# Power.net
KiCad netlist of a schematic drawn in Altium Designer
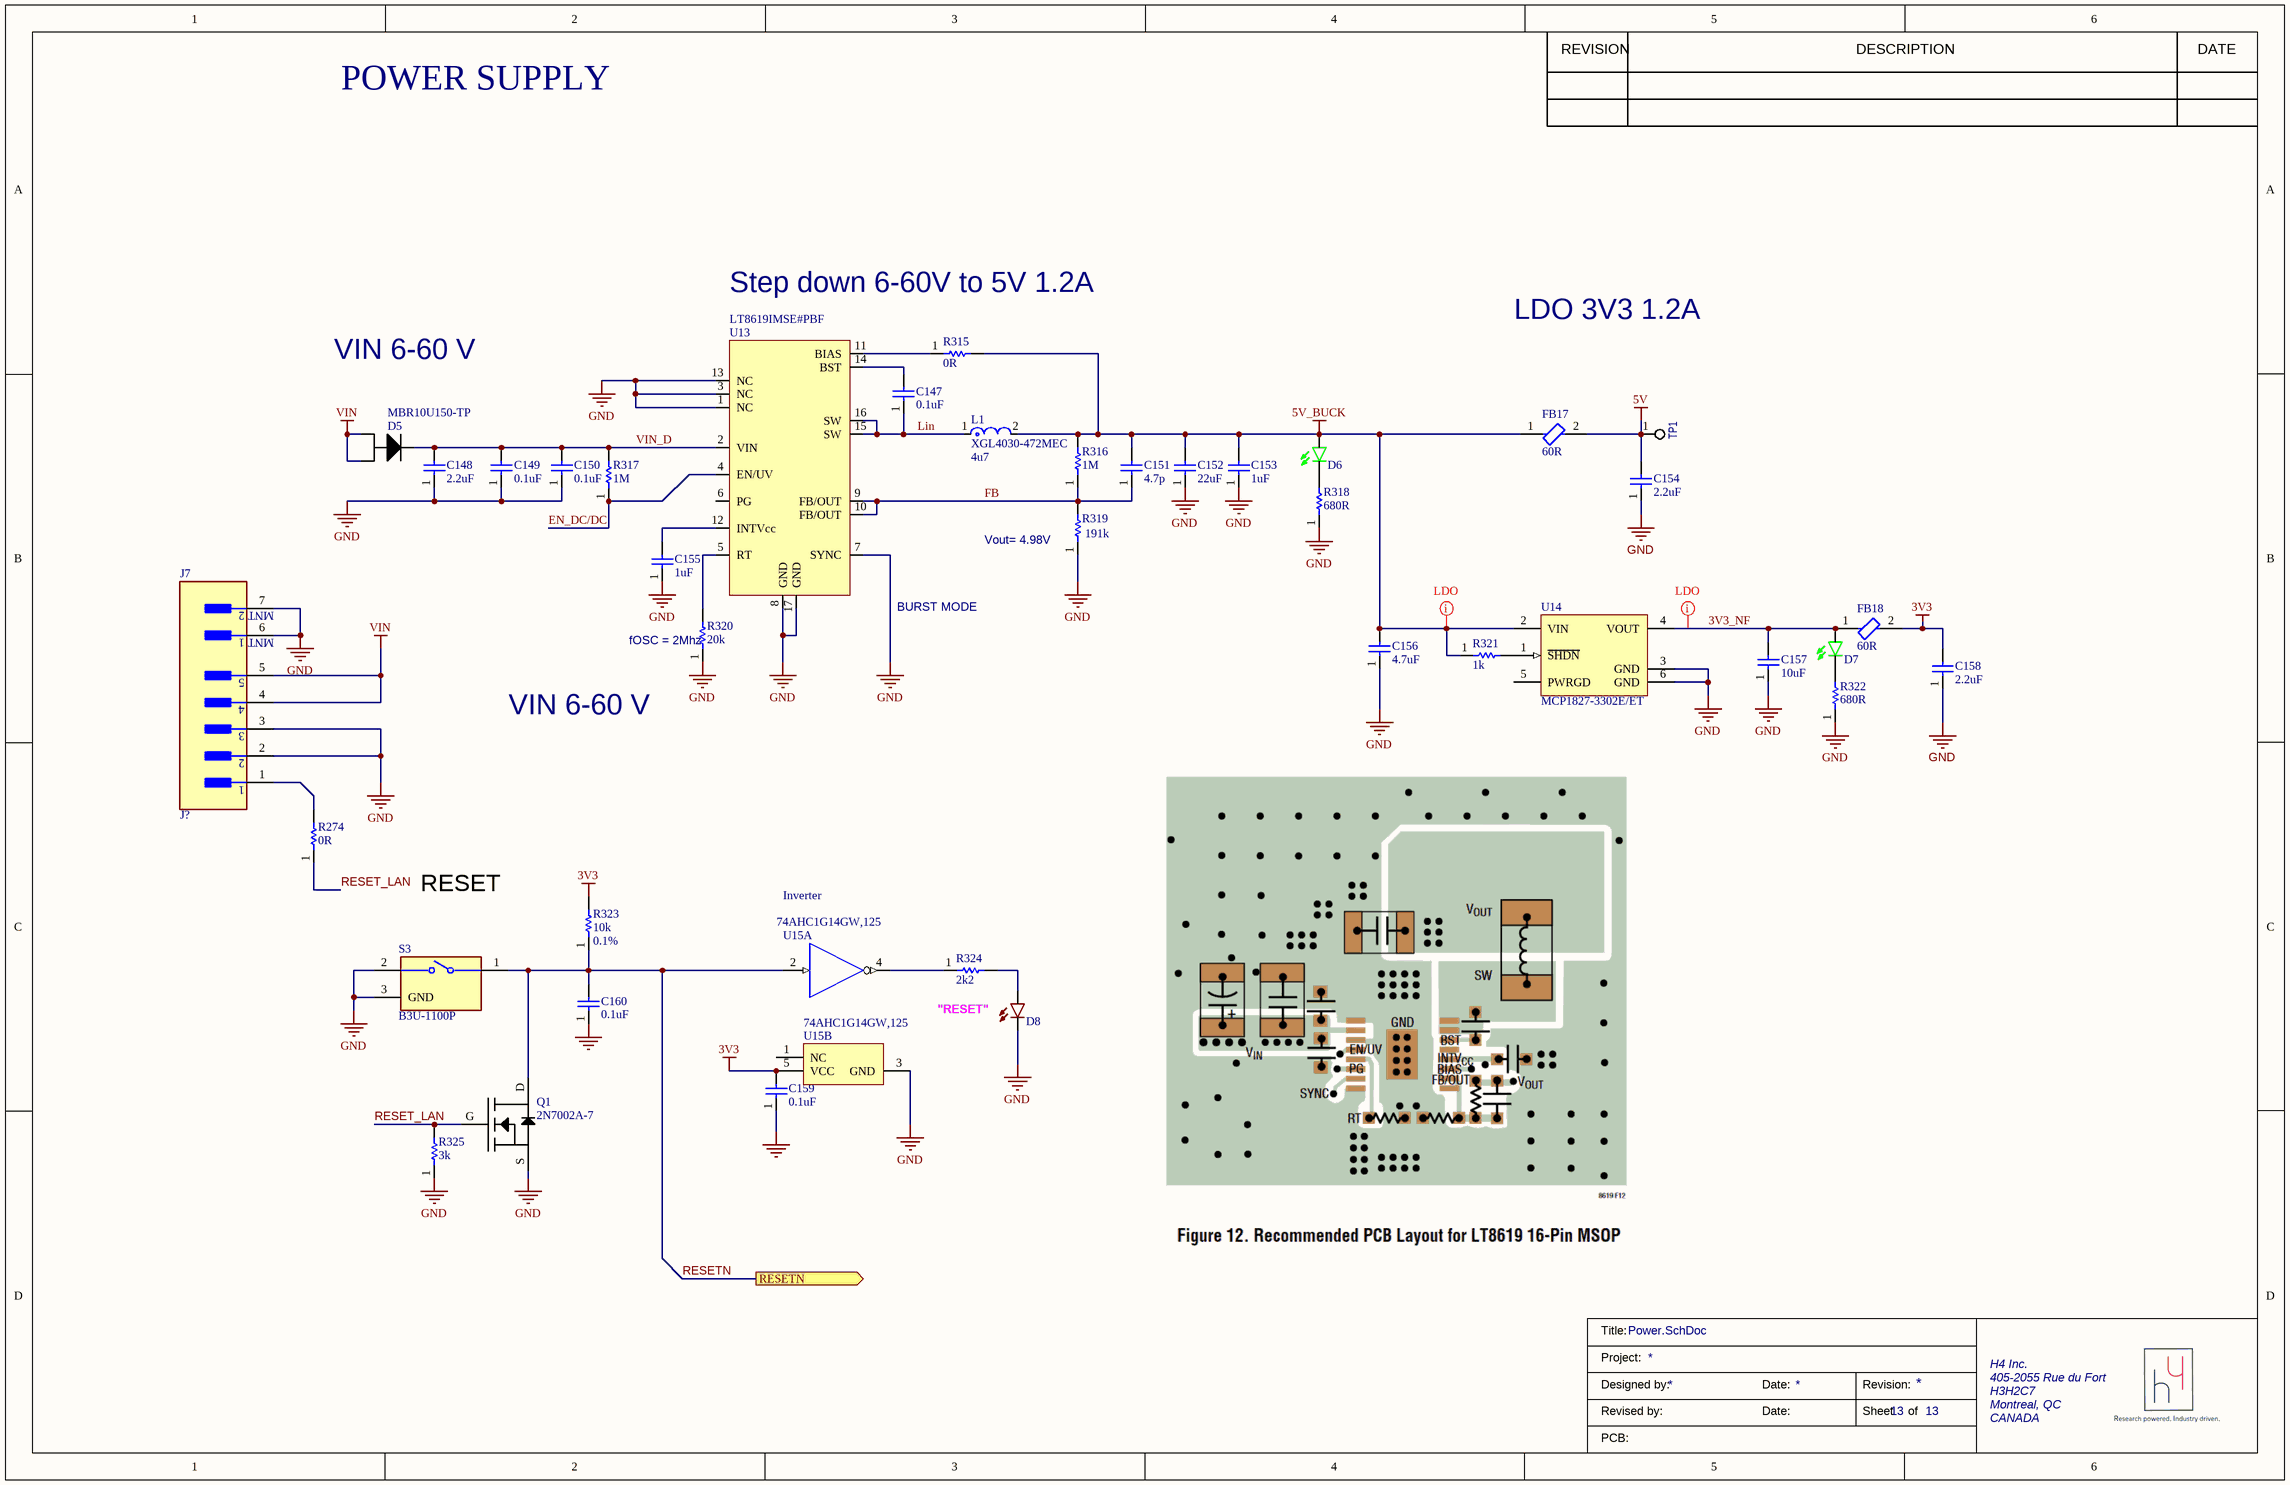
[diagram p0: Power.SchDoc]

(export (version "E")
  (design (tool "Eeschema 10.0.6"))
  (components
    (comp (ref "C147")
      (value "0.1uF")
      (footprint "CAPC1608X09N(0603)")
      (description "CAP CER 0.1UF 100V X7R 0603")
      (fields (field (name "MPN") "CL10B104KC8NNNC") (field (name "TOLERANCE") "10%"))
      (libsource (lib "IHMC_Altium_Lib") (part "0.1uF_100V_0603_CAP"))
    )
    (comp (ref "C148")
      (value "2.2uF")
      (footprint "CAPC3216X16N(1206)")
      (description "CAP CER 2.2UF 100V X7S 1206")
      (fields (field (name "MPN") "C3216X7S2A225K160AB") (field (name "TOLERANCE") "10%"))
      (libsource (lib "IHMC_Altium_Lib") (part "2.2uF_100V_1206_Cap"))
    )
    (comp (ref "C149")
      (value "0.1uF")
      (footprint "CAPC1608X09N(0603)")
      (description "CAP CER 0.1UF 100V X7R 0603")
      (fields (field (name "MPN") "CL10B104KC8NNNC") (field (name "TOLERANCE") "10%"))
      (libsource (lib "IHMC_Altium_Lib") (part "0.1uF_100V_0603_CAP"))
    )
    (comp (ref "C150")
      (value "0.1uF")
      (footprint "CAPC1608X09N(0603)")
      (description "CAP CER 0.1UF 100V X7R 0603")
      (fields (field (name "MPN") "CL10B104KC8NNNC") (field (name "TOLERANCE") "10%"))
      (libsource (lib "IHMC_Altium_Lib") (part "0.1uF_100V_0603_CAP"))
    )
    (comp (ref "C151")
      (value "4.7p")
      (footprint "0402_C")
      (fields
        (field (name "MANUFACTURER") "TDK")
        (field (name "MANUFACTURER PART NUMBER") "CGA2B2C0G1H4R7C050BA")
      )
      (libsource (lib "IHMC_Altium_Lib") (part "4p7_0402_50V_C0G_  CGA2B2C0G1H4R7C050BA"))
    )
    (comp (ref "C152")
      (value "22uF")
      (footprint "CAPC1608X09N(0603)")
      (description "CAP CER 22UF 10V X5R 0603")
      (fields (field (name "MPN") "C1608X5R1A226M080AC") (field (name "TOLERANCE") "20%"))
      (libsource (lib "IHMC_Altium_Lib") (part "22uF_10V_0603_CAP"))
    )
    (comp (ref "C153")
      (value "1uF")
      (footprint "CAPC1608X09N(0603)")
      (description "MLCC - SMD/SMT 25volts 1uF X5R 10%")
      (fields
        (field (name "MPN") "C0603C105K3PACTU")
        (field (name "VOLTAGE") "25VDC")
        (field (name "DRAWN BY") "TC")
      )
      (libsource (lib "IHMC_Altium_Lib") (part "1uF_25VDC_0603_Cap"))
    )
    (comp (ref "C154")
      (value "2.2uF")
      (footprint "CAPC1608X09N(0603)")
      (description "CAP CER 2.2UF 10V X5R 0603")
      (fields (field (name "MPN") "GRM188R61A225KE34D") (field (name "TOLERANCE") "10%"))
      (libsource (lib "IHMC_Altium_Lib") (part "2.2uF_10V_0603_CAP"))
    )
    (comp (ref "C155")
      (value "1uF")
      (footprint "CAPC1608X09N(0603)")
      (description "MLCC - SMD/SMT 25volts 1uF X5R 10%")
      (fields
        (field (name "MPN") "C0603C105K3PACTU")
        (field (name "VOLTAGE") "25VDC")
        (field (name "DRAWN BY") "TC")
      )
      (libsource (lib "IHMC_Altium_Lib") (part "1uF_25VDC_0603_Cap"))
    )
    (comp (ref "C156")
      (value "4.7uF")
      (footprint "CAPC1608X09N(0603)")
      (description "CAP CER 4.7UF 10V X5R 0603")
      (fields (field (name "MPN") "CL10A475KP8NNNC"))
      (libsource (lib "IHMC_Altium_Lib") (part "4.7uF_10V_0603_CAP"))
    )
    (comp (ref "C157")
      (value "10uF")
      (footprint "CAPC3216X16N(1206)")
      (description "MLCC - SMD/SMT 1206 10uF 35volts")
      (fields
        (field (name "MPN") "GRM319R6YA106KA12D")
        (field (name "VOLTAGE") "35VDC")
        (field (name "DRAWN BY") "TC")
      )
      (libsource (lib "IHMC_Altium_Lib") (part "10uF_35VDC_1206_Cap"))
    )
    (comp (ref "C158")
      (value "2.2uF")
      (footprint "CAPC1608X09N(0603)")
      (description "CAP CER 2.2UF 10V X5R 0603")
      (fields (field (name "MPN") "GRM188R61A225KE34D") (field (name "TOLERANCE") "10%"))
      (libsource (lib "IHMC_Altium_Lib") (part "2.2uF_10V_0603_CAP"))
    )
    (comp (ref "C159")
      (value "0.1uF")
      (footprint "CAPC1608X09N(0603)")
      (description "CAP CER 0.1UF 50V X7R 0603")
      (fields (field (name "MPN") "C0603C104K5RACTU") (field (name "VOLTAGE") "50VDC"))
      (libsource (lib "IHMC_Altium_Lib") (part "0.1uF_50V_0603_MLCC"))
    )
    (comp (ref "C160")
      (value "0.1uF")
      (footprint "CAPC1608X09N(0603)")
      (description "CAP CER 0.1UF 50V X7R 0603")
      (fields (field (name "MPN") "C0603C104K5RACTU") (field (name "VOLTAGE") "50VDC"))
      (libsource (lib "IHMC_Altium_Lib") (part "0.1uF_50V_0603_MLCC"))
    )
    (comp (ref "D5")
      (value "MBR10U150-TP")
      (footprint "TO-277")
      (description "Diode Schottky 150V 10A TO277")
      (fields (field (name "MANUFACTURER") "MCC"))
      (libsource (lib "IHMC_Altium_Lib") (part "MBR10U150-TP_SCHOTTKY_150V_10A"))
    )
    (comp (ref "D6")
      (value "LTST-C193KGKT-5A")
      (footprint "LEDC1608X07N(0603)")
      (description "LED GREEN CLEAR CHIP SMD")
      (fields (field (name "DRAWN BY") "TC"))
      (libsource (lib "IHMC_Altium_Lib") (part "GREEN_LED_0603"))
    )
    (comp (ref "D7")
      (value "LTST-C193KGKT-5A")
      (footprint "LEDC1608X07N(0603)")
      (description "LED GREEN CLEAR CHIP SMD")
      (fields (field (name "DRAWN BY") "TC"))
      (libsource (lib "IHMC_Altium_Lib") (part "GREEN_LED_0603"))
    )
    (comp (ref "D8")
      (value "LTST-C193KRKT-5A")
      (footprint "LEDC1608X07N(0603)")
      (description "LED RED CLEAR CHIP SMD")
      (fields (field (name "DRAWN BY") "TC"))
      (libsource (lib "IHMC_Altium_Lib") (part "RED_LED_0603"))
    )
    (comp (ref "FB17")
      (value "BKP2125HS600-T")
      (footprint "FP-BKP2125-IPC_C")
      (fields
        (field (name "TOLERANCE") "25%")
        (field (name "MANUFACTURER") "Taiyo Yuden")
        (field (name "IMPEDANCE") "60R")
      )
      (libsource (lib "IHMC_Altium_Lib") (part "60R_100Mhz_0805_3A"))
    )
    (comp (ref "FB18")
      (value "BKP2125HS600-T")
      (footprint "FP-BKP2125-IPC_C")
      (fields
        (field (name "TOLERANCE") "25%")
        (field (name "MANUFACTURER") "Taiyo Yuden")
        (field (name "IMPEDANCE") "60R")
      )
      (libsource (lib "IHMC_Altium_Lib") (part "60R_100Mhz_0805_3A"))
    )
    (comp (ref "J7")
      (value "J?")
      (footprint "FP-BM05B-GHS-TBT_LF_SN-MFG")
      (description "GH Series 5 Circuits 1.25 mm Pitch Disconnectable Top Entry Shrouned Header")
      (fields
        (field (name "MANUFACTURER") "JST")
        (field (name "MANUFACTURER PART NUMBER") "BM05B-GHS-TBT(LF)(SN)(N)")
      )
      (libsource (lib "IHMC_Altium_Lib") (part "BM05B-GHS-TBT_5POS_JST_GH"))
    )
    (comp (ref "L1")
      (value "XGL4030-472MEC")
      (footprint "FP-XGL4030-472MEC-MFG")
      (description "Inductor Power Shielded Wirewound 4.7uH 20% 1MHz Composite 6.6A 31.5mOhm DCR Automotive T/R")
      (fields (field (name "ALTIUM_VALUE") "4u7") (field (name "MPN") "XGL4030-472"))
      (libsource (lib "IHMC_Altium_Lib") (part "XGL4030-472MEC_4u7_2A1_IND"))
    )
    (comp (ref "Q1")
      (value "2N7002A-7")
      (footprint "SOT95P230X110-3N")
      (description "MOSFET N-CH 60V 0.18A SOT23")
      (libsource (lib "IHMC_Altium_Lib") (part "2N7002_N-MOS"))
    )
    (comp (ref "R274")
      (value "0R")
      (footprint "RESC1608X09N(0603)")
      (description "RES SMD 0 OHM JUMPER 1/10W 0603")
      (fields (field (name "MPN") "RC0603JR-070RL") (field (name "TOLERANCE") "Jumper"))
      (libsource (lib "H4_6-port_EtherCAT_Junction_Module") (part "0R_1/10W_0603_RES"))
    )
    (comp (ref "R315")
      (value "0R")
      (footprint "RESC1608X09N(0603)")
      (description "RES SMD 0 OHM JUMPER 1/10W 0603")
      (fields (field (name "MPN") "RC0603JR-070RL") (field (name "TOLERANCE") "Jumper"))
      (libsource (lib "IHMC_Altium_Lib") (part "0R_1/10W_0603_RES"))
    )
    (comp (ref "R316")
      (value "1M")
      (footprint "RESC1608X09N(0603)")
      (description "RES SMD 1M OHM 1% 1/10W 0603")
      (fields (field (name "MPN") "RC0603FR-071ML") (field (name "TOLERANCE") "1%"))
      (libsource (lib "IHMC_Altium_Lib") (part "1M_1/10W_RES_0603"))
    )
    (comp (ref "R317")
      (value "1M")
      (footprint "RESC1608X09N(0603)")
      (description "RES SMD 1M OHM 1% 1/10W 0603")
      (fields (field (name "MPN") "RC0603FR-071ML") (field (name "TOLERANCE") "1%"))
      (libsource (lib "IHMC_Altium_Lib") (part "1M_1/10W_RES_0603"))
    )
    (comp (ref "R318")
      (value "680R")
      (footprint "RESC1608X09N(0603)")
      (description "RES SMD 680 OHM 1% 1/10W 0603")
      (fields (field (name "MPN") "RC0603FR-07680RL") (field (name "TOLERANCE") "1%"))
      (libsource (lib "IHMC_Altium_Lib") (part "680R_1/10W_0603_RES"))
    )
    (comp (ref "R319")
      (value "191k")
      (footprint "0402")
      (description "Thick Film Resistors - SMD 0402 191Kohms 1% Tol")
      (fields (field (name "TOLERANCE") "1%") (field (name "MANUFACTURER") "Panasonic"))
      (libsource (lib "IHMC_Altium_Lib") (part "191k_0402_1%_ERJ-2RKF1913X"))
    )
    (comp (ref "R320")
      (value "20k")
      (footprint "0402")
      (description "RES SMD 20K OHM 1% 1/10W 0402")
      (fields
        (field (name "MANUFACTURER") "Panasonic")
        (field (name "MANUFACTURER PART NUMBER") "ERJ-2RKF2002X")
      )
      (libsource (lib "IHMC_Altium_Lib") (part "20K_0402_1%_ERJ-2RKF2002X_RES"))
    )
    (comp (ref "R321")
      (value "1k")
      (footprint "RESC1608X09N(0603)")
      (description "MD 1/10watt 1.0Kohms 1%")
      (fields (field (name "MPN") "CRCW06031K00FKEA") (field (name "DRAWN BY") "TC"))
      (libsource (lib "IHMC_Altium_Lib") (part "1k_1/10W_RES_0603"))
    )
    (comp (ref "R322")
      (value "680R")
      (footprint "RESC1608X09N(0603)")
      (description "RES SMD 680 OHM 1% 1/10W 0603")
      (fields (field (name "MPN") "RC0603FR-07680RL") (field (name "TOLERANCE") "1%"))
      (libsource (lib "IHMC_Altium_Lib") (part "680R_1/10W_0603_RES"))
    )
    (comp (ref "R323")
      (value "10k")
      (footprint "0603")
      (description "RES SMD 10K OHM 0.1% 1/10W 0603")
      (fields
        (field (name "MANUFACTURER") "Yageo")
        (field (name "MANUFACTURER PART NUMBER") "RT0603BRB0710KL")
        (field (name "TOLERANCE") "0.1%")
      )
      (libsource (lib "IHMC_Altium_Lib") (part "10k_1/10W_0.1%_10ppm_0603_RES"))
    )
    (comp (ref "R324")
      (value "2k2")
      (footprint "RESC1608X09N(0603)")
      (description "RES SMD 2.2K OHM 1% 1/10W 0603")
      (fields (field (name "MPN") "RC0603FR-072K2L") (field (name "TOLERANCE") "1%"))
      (libsource (lib "IHMC_Altium_Lib") (part "2k2_1/10W_0603_RES"))
    )
    (comp (ref "R325")
      (value "3k")
      (footprint "RESC1608X09N(0603)")
      (description "RES SMD 3K OHM 1% 1/10W 0603")
      (fields
        (field (name "MPN") "RC0603FR-073KL")
        (field (name "TOLERANCE") "1%")
        (field (name "DRAWN BY") "TC")
        (field (name "CHECKED BY") "*")
      )
      (libsource (lib "IHMC_Altium_Lib") (part "3k_1/10W_0603_RES"))
    )
    (comp (ref "S3")
      (value "B3U-1100P")
      (footprint "FP-B3U-1100P-MFSWITCH_G")
      (description "Switch Tactile N.O. SPST Round Button Gull Wing 0.05A 12VDC 1.5N SMD Embossed T/R")
      (fields (field (name "MANUFACTURER") "Omron"))
      (libsource (lib "IHMC_Altium_Lib") (part "SWITCH_SPST_NO_B3U-1100P"))
    )
    (comp (ref "TP1")
      (value "TP_SMD")
      (footprint "Pad_1mm")
      (description "Test point SMD")
      (libsource (lib "H4_6-port_EtherCAT_Junction_Module") (part "TP_SMD_1MM"))
    )
    (comp (ref "U13")
      (value "LT8619IMSE#PBF")
      (footprint "SOP50P490X110-17N")
      (description "LT8619 - 60V, 1.2A Synchronous Monolithic Buck Regulator with 6µA Quiescent Current")
      (fields (field (name "MANUFACTURER") "Analog Devices / Linear Technology"))
      (libsource (lib "IHMC_Altium_Lib") (part "LT8619IMSE#PBF_BUCK_60V_1A2"))
    )
    (comp (ref "U14")
      (value "MCP1827-3302E/ET")
      (footprint "5-DDPAK _Model2")
      (description "MCP1827-3302E/ET; LDOVoltage Regulator; 1.5A; 3.3V +/-2%; 2.3 to 6Vin; 5-Pin D2PAK")
      (fields (field (name "MANUFACTURER") "Microchip"))
      (libsource (lib "IHMC_Converters_Regulators") (part "3V3_LDO_1A5_MCP1827-3302E/ET"))
    )
    (comp (ref "U15")
      (value "74AHC1G14GW,125")
      (footprint "NXP-SOT353-1_L_TSSOP5")
      (description "74AHC1G14GW/UMT5/REELR//")
      (fields
        (field (name "MANUFACTURER") "NXP Semiconductors")
        (field (name "MANUFACTURER PART NUMBER") "74AHC1G14GW125")
      )
      (libsource (lib "IHMC_Altium_Lib") (part "74AHC1G14GW,125_INVERTER_SCHMITT_5TSSOP"))
    )
  )
  (nets
    (net (code "1") (name "/3V3_NF") (class "Default")
      (node (ref "C157") (pin "2") (pinfunction "2_2") (pintype "passive"))
      (node (ref "D7") (pin "A") (pinfunction "A_A") (pintype "passive"))
      (node (ref "FB18") (pin "1") (pinfunction "1_1") (pintype "passive"))
      (node (ref "U14") (pin "4") (pinfunction "VOUT_4") (pintype "power_in"))
    )
    (net (code "2") (name "/EN_DC{slash}DC") (class "Default")
      (node (ref "R317") (pin "1") (pinfunction "1_1") (pintype "passive"))
      (node (ref "U13") (pin "4") (pinfunction "EN/UV_4") (pintype "passive"))
    )
    (net (code "3") (name "/FB") (class "Default")
      (node (ref "C151") (pin "1") (pinfunction "1_1") (pintype "passive"))
      (node (ref "R316") (pin "1") (pinfunction "1_1") (pintype "passive"))
      (node (ref "R319") (pin "2") (pinfunction "2_2") (pintype "passive"))
      (node (ref "U13") (pin "10") (pinfunction "FB/OUT_10") (pintype "passive"))
      (node (ref "U13") (pin "9") (pinfunction "FB/OUT_9") (pintype "passive"))
    )
    (net (code "4") (name "/Lin") (class "Default")
      (node (ref "C147") (pin "1") (pinfunction "1_1") (pintype "passive"))
      (node (ref "L1") (pin "1") (pinfunction "1_1") (pintype "passive"))
      (node (ref "U13") (pin "15") (pinfunction "SW_15") (pintype "passive"))
      (node (ref "U13") (pin "16") (pinfunction "SW_16") (pintype "passive"))
    )
    (net (code "5") (name "/RESETN") (class "Default")
      (node (ref "C160") (pin "2") (pinfunction "2_2") (pintype "passive"))
      (node (ref "Q1") (pin "D") (pinfunction "3_D") (pintype "passive"))
      (node (ref "R323") (pin "1") (pinfunction "1_1") (pintype "passive"))
      (node (ref "S3") (pin "1") (pinfunction "1_1") (pintype "passive"))
      (node (ref "U15") (pin "2") (pinfunction "A_2") (pintype "input"))
    )
    (net (code "6") (name "/RESET_LAN") (class "Default")
      (node (ref "Q1") (pin "G") (pinfunction "2_G") (pintype "passive"))
      (node (ref "R274") (pin "1") (pinfunction "1_1") (pintype "passive"))
      (node (ref "R325") (pin "2") (pinfunction "2_2") (pintype "passive"))
    )
    (net (code "7") (name "/VIN_D") (class "Default")
      (node (ref "C148") (pin "2") (pinfunction "2_2") (pintype "passive"))
      (node (ref "C149") (pin "2") (pinfunction "2_2") (pintype "passive"))
      (node (ref "C150") (pin "2") (pinfunction "2_2") (pintype "passive"))
      (node (ref "D5") (pin "3") (pinfunction "3_3") (pintype "passive"))
      (node (ref "R317") (pin "2") (pinfunction "2_2") (pintype "passive"))
      (node (ref "U13") (pin "2") (pinfunction "VIN_2") (pintype "passive"))
    )
    (net (code "8") (name "3V3") (class "Default")
      (node (ref "C158") (pin "2") (pinfunction "2_2") (pintype "passive"))
      (node (ref "C159") (pin "2") (pinfunction "2_2") (pintype "passive"))
      (node (ref "FB18") (pin "2") (pinfunction "2_2") (pintype "passive"))
      (node (ref "R323") (pin "2") (pinfunction "2_2") (pintype "passive"))
      (node (ref "U15") (pin "5") (pinfunction "VCC_5") (pintype "power_in"))
    )
    (net (code "9") (name "5V") (class "Default")
      (node (ref "C154") (pin "2") (pinfunction "2_2") (pintype "passive"))
      (node (ref "FB17") (pin "2") (pinfunction "2_2") (pintype "passive"))
      (node (ref "TP1") (pin "1") (pinfunction "IN_1") (pintype "passive"))
    )
    (net (code "10") (name "5V_BUCK") (class "Default")
      (node (ref "C151") (pin "2") (pinfunction "2_2") (pintype "passive"))
      (node (ref "C152") (pin "2") (pinfunction "2_2") (pintype "passive"))
      (node (ref "C153") (pin "2") (pinfunction "2_2") (pintype "passive"))
      (node (ref "C156") (pin "2") (pinfunction "2_2") (pintype "passive"))
      (node (ref "D6") (pin "A") (pinfunction "A_A") (pintype "passive"))
      (node (ref "FB17") (pin "1") (pinfunction "1_1") (pintype "passive"))
      (node (ref "L1") (pin "2") (pinfunction "2_2") (pintype "passive"))
      (node (ref "R315") (pin "2") (pinfunction "2_2") (pintype "passive"))
      (node (ref "R316") (pin "2") (pinfunction "2_2") (pintype "passive"))
      (node (ref "R321") (pin "1") (pinfunction "1_1") (pintype "passive"))
      (node (ref "U14") (pin "2") (pinfunction "VIN_2") (pintype "power_in"))
    )
    (net (code "11") (name "GND") (class "Default")
      (node (ref "C148") (pin "1") (pinfunction "1_1") (pintype "passive"))
      (node (ref "C149") (pin "1") (pinfunction "1_1") (pintype "passive"))
      (node (ref "C150") (pin "1") (pinfunction "1_1") (pintype "passive"))
      (node (ref "C152") (pin "1") (pinfunction "1_1") (pintype "passive"))
      (node (ref "C153") (pin "1") (pinfunction "1_1") (pintype "passive"))
      (node (ref "C154") (pin "1") (pinfunction "1_1") (pintype "passive"))
      (node (ref "C155") (pin "1") (pinfunction "1_1") (pintype "passive"))
      (node (ref "C156") (pin "1") (pinfunction "1_1") (pintype "passive"))
      (node (ref "C157") (pin "1") (pinfunction "1_1") (pintype "passive"))
      (node (ref "C158") (pin "1") (pinfunction "1_1") (pintype "passive"))
      (node (ref "C159") (pin "1") (pinfunction "1_1") (pintype "passive"))
      (node (ref "C160") (pin "1") (pinfunction "1_1") (pintype "passive"))
      (node (ref "D8") (pin "C") (pinfunction "C_C") (pintype "passive"))
      (node (ref "J7") (pin "2") (pinfunction "2_2") (pintype "passive"))
      (node (ref "J7") (pin "3") (pinfunction "3_3") (pintype "passive"))
      (node (ref "J7") (pin "6") (pinfunction "MNT_1_6") (pintype "passive"))
      (node (ref "J7") (pin "7") (pinfunction "MNT_2_7") (pintype "passive"))
      (node (ref "Q1") (pin "S") (pinfunction "1_S") (pintype "passive"))
      (node (ref "R318") (pin "1") (pinfunction "1_1") (pintype "passive"))
      (node (ref "R319") (pin "1") (pinfunction "1_1") (pintype "passive"))
      (node (ref "R320") (pin "1") (pinfunction "1_1") (pintype "passive"))
      (node (ref "R322") (pin "1") (pinfunction "1_1") (pintype "passive"))
      (node (ref "R325") (pin "1") (pinfunction "1_1") (pintype "passive"))
      (node (ref "S3") (pin "2") (pinfunction "2_2") (pintype "passive"))
      (node (ref "S3") (pin "3") (pinfunction "GND_3") (pintype "power_in"))
      (node (ref "U13") (pin "1") (pinfunction "NC_1") (pintype "passive"))
      (node (ref "U13") (pin "13") (pinfunction "NC_13") (pintype "passive"))
      (node (ref "U13") (pin "17") (pinfunction "GND_17") (pintype "passive"))
      (node (ref "U13") (pin "3") (pinfunction "NC_3") (pintype "passive"))
      (node (ref "U13") (pin "7") (pinfunction "SYNC_7") (pintype "passive"))
      (node (ref "U13") (pin "8") (pinfunction "GND_8") (pintype "passive"))
      (node (ref "U14") (pin "3") (pinfunction "GND_3") (pintype "power_in"))
      (node (ref "U14") (pin "6") (pinfunction "GND_6") (pintype "power_in"))
      (node (ref "U15") (pin "3") (pinfunction "GND_3") (pintype "power_in"))
    )
    (net (code "12") (name "Net-(D6-PadC)") (class "Default")
      (node (ref "D6") (pin "C") (pinfunction "C_C") (pintype "passive"))
      (node (ref "R318") (pin "2") (pinfunction "2_2") (pintype "passive"))
    )
    (net (code "13") (name "Net-(D7-PadC)") (class "Default")
      (node (ref "D7") (pin "C") (pinfunction "C_C") (pintype "passive"))
      (node (ref "R322") (pin "2") (pinfunction "2_2") (pintype "passive"))
    )
    (net (code "14") (name "Net-(D8-PadA)") (class "Default")
      (node (ref "D8") (pin "A") (pinfunction "A_A") (pintype "passive"))
      (node (ref "R324") (pin "2") (pinfunction "2_2") (pintype "passive"))
    )
    (net (code "15") (name "Net-(J7-Pad1)") (class "Default")
      (node (ref "J7") (pin "1") (pinfunction "1_1") (pintype "passive"))
      (node (ref "R274") (pin "2") (pinfunction "2_2") (pintype "passive"))
    )
    (net (code "16") (name "Net-(U13-BIAS)") (class "Default")
      (node (ref "R315") (pin "1") (pinfunction "1_1") (pintype "passive"))
      (node (ref "U13") (pin "11") (pinfunction "BIAS_11") (pintype "passive"))
    )
    (net (code "17") (name "Net-(U13-BST)") (class "Default")
      (node (ref "C147") (pin "2") (pinfunction "2_2") (pintype "passive"))
      (node (ref "U13") (pin "14") (pinfunction "BST_14") (pintype "passive"))
    )
    (net (code "18") (name "Net-(U13-INTVcc)") (class "Default")
      (node (ref "C155") (pin "2") (pinfunction "2_2") (pintype "passive"))
      (node (ref "U13") (pin "12") (pinfunction "INTVcc_12") (pintype "passive"))
    )
    (net (code "19") (name "Net-(U13-RT)") (class "Default")
      (node (ref "R320") (pin "2") (pinfunction "2_2") (pintype "passive"))
      (node (ref "U13") (pin "5") (pinfunction "RT_5") (pintype "passive"))
    )
    (net (code "20") (name "Net-(U14-~{SHDN})") (class "Default")
      (node (ref "R321") (pin "2") (pinfunction "2_2") (pintype "passive"))
      (node (ref "U14") (pin "1") (pinfunction "~{SHDN}_1") (pintype "input"))
    )
    (net (code "21") (name "Net-(U15A-~{Y})") (class "Default")
      (node (ref "R324") (pin "1") (pinfunction "1_1") (pintype "passive"))
      (node (ref "U15") (pin "4") (pinfunction "~{Y}_4") (pintype "output"))
    )
    (net (code "22") (name "VIN") (class "Default")
      (node (ref "D5") (pin "1") (pinfunction "1_1") (pintype "passive"))
      (node (ref "D5") (pin "2") (pinfunction "2_2") (pintype "passive"))
      (node (ref "J7") (pin "4") (pinfunction "4_4") (pintype "passive"))
      (node (ref "J7") (pin "5") (pinfunction "5_5") (pintype "passive"))
    )
    (net (code "23") (name "unconnected-(U13-PG-Pad6)") (class "Default")
      (node (ref "U13") (pin "6") (pinfunction "PG_6") (pintype "passive"))
    )
    (net (code "24") (name "unconnected-(U14-PWRGD-Pad5)") (class "Default")
      (node (ref "U14") (pin "5") (pinfunction "PWRGD_5") (pintype "power_in"))
    )
    (net (code "25") (name "unconnected-(U15B-NC-Pad1)") (class "Default")
      (node (ref "U15") (pin "1") (pinfunction "NC_1") (pintype "passive"))
    )
  )
)
